# imu.net
KiCad netlist of a schematic drawn in Altium Designer
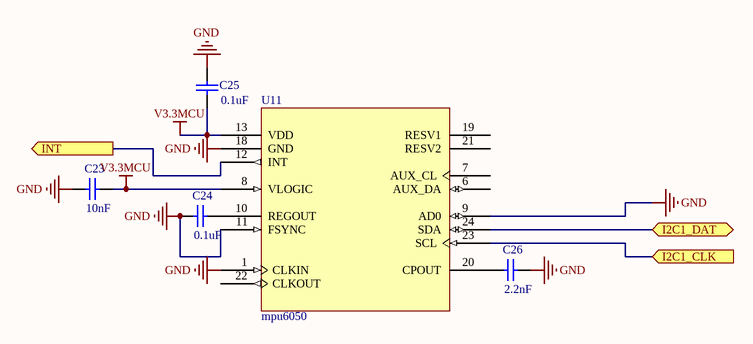
[diagram p0: imu.SchDoc]

(export (version "E")
  (design (tool "Eeschema 10.0.6"))
  (components
    (comp (ref "C23")
      (value "10nF")
      (footprint "1608[0603]")
      (description "Capacitor (Semiconductor SIM Model)")
      (fields (field (name "PUBLISHER") "Altium Limited"))
      (libsource (lib "Miscellaneous Devices") (part "Cap Semi"))
    )
    (comp (ref "C24")
      (value "0.1uF")
      (footprint "1608[0603]")
      (description "Capacitor (Semiconductor SIM Model)")
      (fields (field (name "PUBLISHER") "Altium Limited"))
      (libsource (lib "Miscellaneous Devices") (part "Cap Semi"))
    )
    (comp (ref "C25")
      (value "0.1uF")
      (footprint "1608[0603]")
      (description "Capacitor (Semiconductor SIM Model)")
      (fields (field (name "PUBLISHER") "Altium Limited"))
      (libsource (lib "Miscellaneous Devices") (part "Cap Semi"))
    )
    (comp (ref "C26")
      (value "2.2nF")
      (footprint "1608[0603]")
      (description "Capacitor (Semiconductor SIM Model)")
      (fields (field (name "PUBLISHER") "Altium Limited"))
      (libsource (lib "Miscellaneous Devices") (part "Cap Semi"))
    )
    (comp (ref "U11")
      (value "mpu6050")
      (footprint "QFN-24_N")
      (libsource (lib "KyliesParts") (part "mpu6050"))
    )
  )
  (nets
    (net (code "1") (name "/I2C1_CLK") (class "Default")
      (node (ref "U11") (pin "23") (pinfunction "SCL_23") (pintype "input"))
    )
    (net (code "2") (name "/I2C1_DAT") (class "Default")
      (node (ref "U11") (pin "24") (pinfunction "SDA_24") (pintype "bidirectional"))
    )
    (net (code "3") (name "/INT") (class "Default")
      (node (ref "U11") (pin "12") (pinfunction "INT_12") (pintype "output"))
    )
    (net (code "4") (name "GND") (class "Default")
      (node (ref "C23") (pin "1") (pinfunction "1_1") (pintype "passive"))
      (node (ref "C24") (pin "1") (pinfunction "1_1") (pintype "passive"))
      (node (ref "C25") (pin "2") (pinfunction "2_2") (pintype "passive"))
      (node (ref "C26") (pin "2") (pinfunction "2_2") (pintype "passive"))
      (node (ref "U11") (pin "1") (pinfunction "CLKIN_1") (pintype "input"))
      (node (ref "U11") (pin "11") (pinfunction "FSYNC_11") (pintype "input"))
      (node (ref "U11") (pin "18") (pinfunction "GND_18") (pintype "power_in"))
      (node (ref "U11") (pin "9") (pinfunction "AD0_9") (pintype "bidirectional"))
    )
    (net (code "5") (name "Net-(U11-CPOUT)") (class "Default")
      (node (ref "C26") (pin "1") (pinfunction "1_1") (pintype "passive"))
      (node (ref "U11") (pin "20") (pinfunction "CPOUT_20") (pintype "passive"))
    )
    (net (code "6") (name "Net-(U11-REGOUT)") (class "Default")
      (node (ref "C24") (pin "2") (pinfunction "2_2") (pintype "passive"))
      (node (ref "U11") (pin "10") (pinfunction "REGOUT_10") (pintype "passive"))
    )
    (net (code "7") (name "V3.3MCU") (class "Default")
      (node (ref "C23") (pin "2") (pinfunction "2_2") (pintype "passive"))
      (node (ref "C25") (pin "1") (pinfunction "1_1") (pintype "passive"))
      (node (ref "U11") (pin "13") (pinfunction "VDD_13") (pintype "power_in"))
      (node (ref "U11") (pin "8") (pinfunction "VLOGIC_8") (pintype "input"))
    )
    (net (code "8") (name "unconnected-(U11-AUX_CL-Pad7)") (class "Default")
      (node (ref "U11") (pin "7") (pinfunction "AUX_CL_7") (pintype "passive"))
    )
    (net (code "9") (name "unconnected-(U11-AUX_DA-Pad6)") (class "Default")
      (node (ref "U11") (pin "6") (pinfunction "AUX_DA_6") (pintype "bidirectional"))
    )
    (net (code "10") (name "unconnected-(U11-CLKOUT-Pad22)") (class "Default")
      (node (ref "U11") (pin "22") (pinfunction "CLKOUT_22") (pintype "output"))
    )
    (net (code "11") (name "unconnected-(U11-RESV1-Pad19)") (class "Default")
      (node (ref "U11") (pin "19") (pinfunction "RESV1_19") (pintype "passive"))
    )
    (net (code "12") (name "unconnected-(U11-RESV2-Pad21)") (class "Default")
      (node (ref "U11") (pin "21") (pinfunction "RESV2_21") (pintype "passive"))
    )
  )
)
